# STM32.net
KiCad netlist of a schematic drawn in Altium Designer
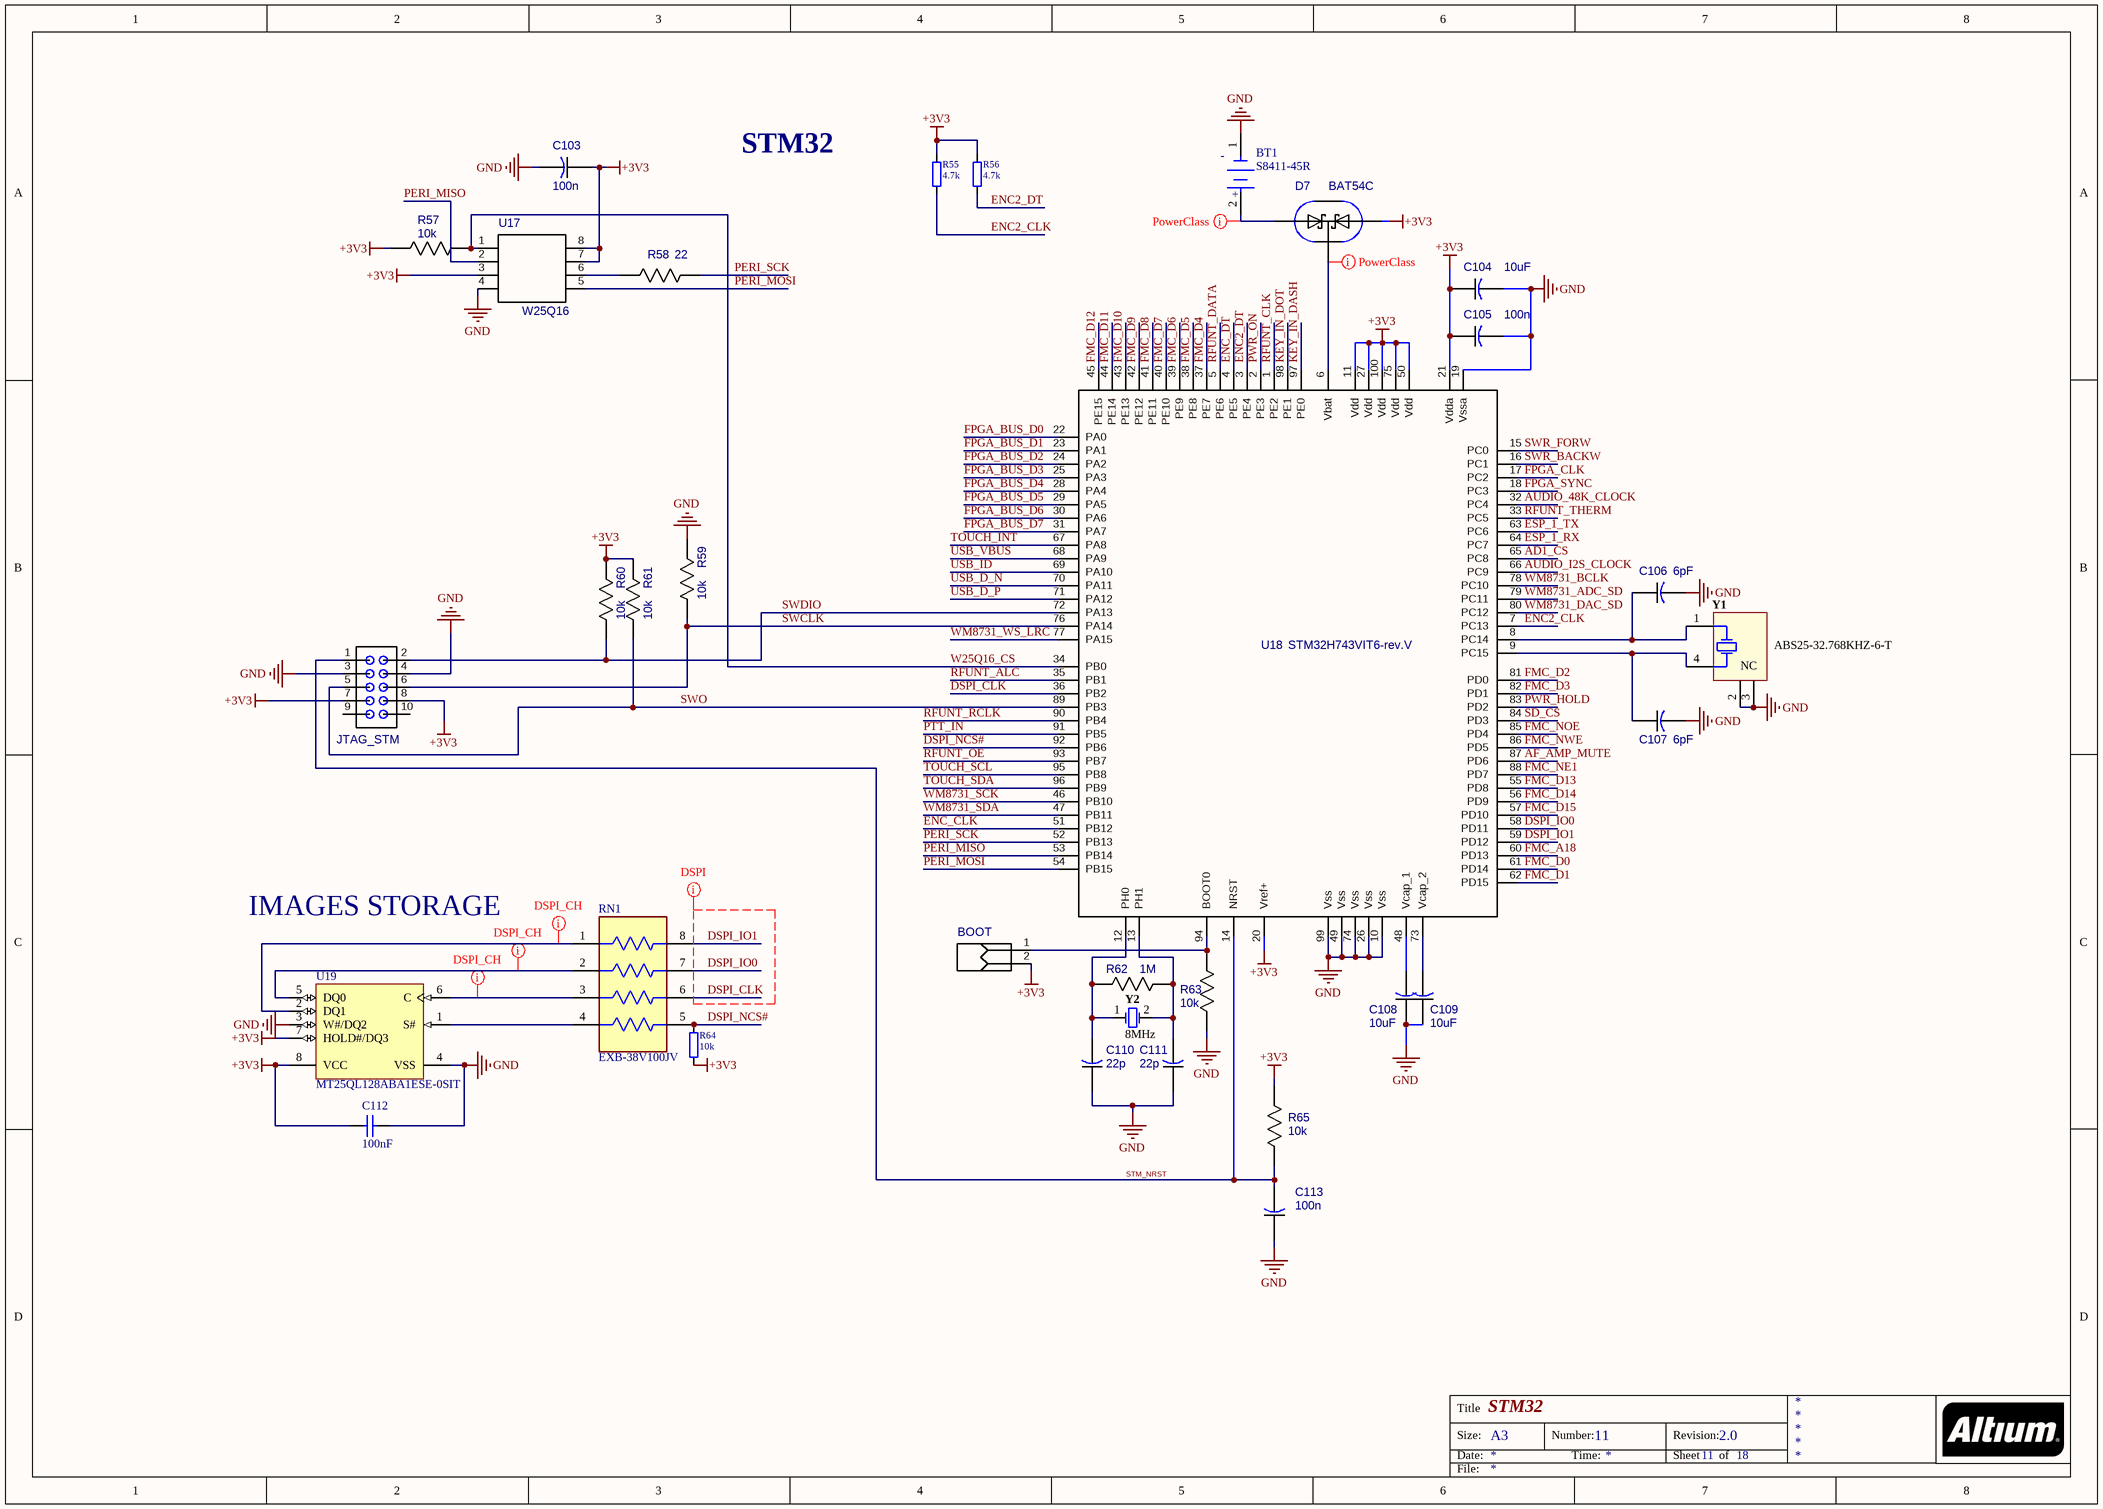
[diagram p0: STM32.SchDoc]

(export (version "E")
  (design (tool "Eeschema 10.0.6"))
  (components
    (comp (ref "BOOT")
      (value "~")
      (footprint "51022-0200")
      (description "2 Pin")
      (libsource (lib "*") (part "51022-0200"))
    )
    (comp (ref "BT1")
      (value "S8411-45R")
      (footprint "FP-S8411-45R-MFG")
      (description "BATTERY HOLDER COIN 12MM SMD")
      (libsource (lib "Altium Content Vault") (part "60d3b5b901a8747834971d0eb8cf3fd"))
    )
    (comp (ref "C103")
      (value "100n")
      (footprint "CAP_0805")
      (description "CAP_0805")
      (libsource (lib "*") (part "CAP_0805"))
    )
    (comp (ref "C104")
      (value "10uF")
      (footprint "CAP_0805")
      (description "CAP_0805")
      (libsource (lib "*") (part "CAP_0805"))
    )
    (comp (ref "C105")
      (value "100n")
      (footprint "CAP_0805")
      (description "CAP_0805")
      (libsource (lib "*") (part "CAP_0805"))
    )
    (comp (ref "C106")
      (value "6pF")
      (footprint "CAP_0805")
      (description "CAP_0805")
      (libsource (lib "*") (part "CAP_0805"))
    )
    (comp (ref "C107")
      (value "6pF")
      (footprint "CAP_0805")
      (description "CAP_0805")
      (libsource (lib "*") (part "CAP_0805"))
    )
    (comp (ref "C108")
      (value "10uF")
      (footprint "CAP_0805")
      (description "CAP_0805")
      (libsource (lib "*") (part "CAP_0805"))
    )
    (comp (ref "C109")
      (value "10uF")
      (footprint "CAP_0805")
      (description "CAP_0805")
      (libsource (lib "*") (part "CAP_0805"))
    )
    (comp (ref "C110")
      (value "22p")
      (footprint "CAP_0805")
      (description "CAP_0805")
      (libsource (lib "*") (part "CAP_0805"))
    )
    (comp (ref "C111")
      (value "22p")
      (footprint "CAP_0805")
      (description "CAP_0805")
      (libsource (lib "*") (part "CAP_0805"))
    )
    (comp (ref "C112")
      (value "100nF")
      (footprint "C-0805")
      (description "Ceramic Multilayer Capacitor")
      (fields (field (name "MANUFACTURER") "Yageo/Phycomp") (field (name "TOLERANCE") "±10%"))
      (libsource (lib "Hristo") (part "C semi"))
    )
    (comp (ref "C113")
      (value "100n")
      (footprint "CAP_0805")
      (description "CAP_0805")
      (libsource (lib "*") (part "CAP_0805"))
    )
    (comp (ref "D7") (value "BAT54C") (footprint "BAT54C") (libsource (lib "*") (part "BAT54C")))
    (comp (ref "JTAG_STM")
      (value "~")
      (footprint "IDC10")
      (description "2*5 Pin")
      (libsource (lib "*") (part "IDC10"))
    )
    (comp (ref "R55")
      (value "4.7k")
      (footprint "R-0603")
      (description "Chip Resistor")
      (fields (field (name "MANUFACTURER") "Yageo/Phycomp"))
      (libsource (lib "Hristo") (part "RES semi"))
    )
    (comp (ref "R56")
      (value "4.7k")
      (footprint "R-0603")
      (description "Chip Resistor")
      (fields (field (name "MANUFACTURER") "Yageo/Phycomp"))
      (libsource (lib "Hristo") (part "RES semi"))
    )
    (comp (ref "R57")
      (value "10k")
      (footprint "RES_0805")
      (description "RES_0805")
      (libsource (lib "*") (part "RES_0805"))
    )
    (comp (ref "R58")
      (value "22")
      (footprint "RES_0805")
      (description "RES_0805")
      (libsource (lib "*") (part "RES_0805"))
    )
    (comp (ref "R59")
      (value "10k")
      (footprint "RES_0805")
      (description "RES_0805")
      (libsource (lib "*") (part "RES_0805"))
    )
    (comp (ref "R60")
      (value "10k")
      (footprint "RES_0805")
      (description "RES_0805")
      (libsource (lib "*") (part "RES_0805"))
    )
    (comp (ref "R61")
      (value "10k")
      (footprint "RES_0805")
      (description "RES_0805")
      (libsource (lib "*") (part "RES_0805"))
    )
    (comp (ref "R62")
      (value "1M")
      (footprint "RES_0805")
      (description "RES_0805")
      (fields (field (name "Comment") "1m"))
      (libsource (lib "*") (part "RES_0805"))
    )
    (comp (ref "R63")
      (value "10k")
      (footprint "RES_0805")
      (description "RES_0805")
      (libsource (lib "*") (part "RES_0805"))
    )
    (comp (ref "R64")
      (value "10k")
      (footprint "R-0603")
      (description "Chip Resistor")
      (fields (field (name "MANUFACTURER") "Yageo/Phycomp"))
      (libsource (lib "Hristo") (part "RES semi"))
    )
    (comp (ref "R65")
      (value "10k")
      (footprint "RES_0805")
      (description "RES_0805")
      (libsource (lib "*") (part "RES_0805"))
    )
    (comp (ref "RN1")
      (value "EXB-38V100JV")
      (footprint "FP-EXB38V-MFG")
      (description "RES ARRAY 4 RES 10 OHM 1206")
      (fields (field (name "TOLERANCE") "5%"))
      (libsource (lib "Altium Content Vault") (part "f16b1fce1dd1e635ae8334856b3239e"))
    )
    (comp (ref "U17") (value "W25Q16") (footprint "W25Q16") (libsource (lib "*") (part "W25Q16")))
    (comp (ref "U18")
      (value "STM32H743VIT6-rev.V")
      (footprint "STM32H743VIT6")
      (description "STM32H743VIT6")
      (libsource (lib "*") (part "STM32H743VIT6"))
    )
    (comp (ref "U19")
      (value "MT25QL128ABA1ESE-0SIT")
      (footprint "MICT-SE-8_M")
      (fields (field (name "MANUFACTURER") "Micron"))
      (libsource (lib "Altium Content Vault") (part "MICT-MT25QL128ABA-SOP2-8"))
    )
    (comp (ref "Y1")
      (value "ABS25-32.768KHZ-6-T")
      (footprint "ABRA-ABS25-4_V")
      (fields (field (name "TOLERANCE") "20PPM") (field (name "MANUFACTURER") "Abracon"))
      (libsource (lib "Altium Content Vault") (part "ABRA-XTAL_1-4-4"))
    )
    (comp (ref "Y2")
      (value "8MHz")
      (footprint "FOX-FOXSLF-2_V")
      (description "Resistance Weld Thru-Hole Crystal, 8 MHz, +/-30 ppm, -20 to 70 degC, 2-Pin THD, RoHS, Bulk")
      (libsource (lib "Altium Content Vault") (part "XTAL-1-2-2"))
    )
  )
  (nets
    (net (code "1") (name "+3V3") (class "Default")
      (node (ref "BOOT") (pin "2") (pinfunction "2_2") (pintype "passive"))
      (node (ref "C103") (pin "1") (pinfunction "1_1") (pintype "passive"))
      (node (ref "C104") (pin "1") (pinfunction "1_1") (pintype "passive"))
      (node (ref "C105") (pin "1") (pinfunction "1_1") (pintype "passive"))
      (node (ref "C112") (pin "1") (pinfunction "1_1") (pintype "passive"))
      (node (ref "D7") (pin "1") (pinfunction "(A1)_1") (pintype "passive"))
      (node (ref "JTAG_STM") (pin "7") (pinfunction "7_7") (pintype "passive"))
      (node (ref "JTAG_STM") (pin "8") (pinfunction "8_8") (pintype "passive"))
      (node (ref "R55") (pin "2") (pinfunction "2_2") (pintype "passive"))
      (node (ref "R56") (pin "2") (pinfunction "2_2") (pintype "passive"))
      (node (ref "R57") (pin "1") (pinfunction "1_1") (pintype "passive"))
      (node (ref "R60") (pin "1") (pinfunction "1_1") (pintype "passive"))
      (node (ref "R61") (pin "1") (pinfunction "1_1") (pintype "passive"))
      (node (ref "R64") (pin "1") (pinfunction "1_1") (pintype "passive"))
      (node (ref "R65") (pin "2") (pinfunction "2_2") (pintype "passive"))
      (node (ref "U17") (pin "3") (pinfunction "WP_3") (pintype "passive"))
      (node (ref "U17") (pin "7") (pinfunction "HOLD_7") (pintype "passive"))
      (node (ref "U17") (pin "8") (pinfunction "VCC_8") (pintype "passive"))
      (node (ref "U18") (pin "100") (pinfunction "Vdd_100") (pintype "passive"))
      (node (ref "U18") (pin "11") (pinfunction "Vdd_11") (pintype "passive"))
      (node (ref "U18") (pin "20") (pinfunction "Vref+_20") (pintype "passive"))
      (node (ref "U18") (pin "21") (pinfunction "Vdda_21") (pintype "passive"))
      (node (ref "U18") (pin "27") (pinfunction "Vdd_27") (pintype "passive"))
      (node (ref "U18") (pin "50") (pinfunction "Vdd_50") (pintype "passive"))
      (node (ref "U18") (pin "75") (pinfunction "Vdd_75") (pintype "passive"))
      (node (ref "U19") (pin "7") (pinfunction "HOLD#/DQ3_7") (pintype "bidirectional"))
      (node (ref "U19") (pin "8") (pinfunction "VCC_8") (pintype "power_in"))
    )
    (net (code "2") (name "/AD1_CS") (class "Default")
      (node (ref "U18") (pin "65") (pinfunction "PC8_65") (pintype "passive"))
    )
    (net (code "3") (name "/AF_AMP_MUTE") (class "Default")
      (node (ref "U18") (pin "87") (pinfunction "PD6_87") (pintype "passive"))
    )
    (net (code "4") (name "/AUDIO_48K_CLOCK") (class "Default")
      (node (ref "U18") (pin "32") (pinfunction "PC4_32") (pintype "passive"))
    )
    (net (code "5") (name "/AUDIO_I2S_CLOCK") (class "Default")
      (node (ref "U18") (pin "66") (pinfunction "PC9_66") (pintype "passive"))
    )
    (net (code "6") (name "/DSPI_CLK") (class "Default")
      (node (ref "RN1") (pin "6") (pinfunction "6_6") (pintype "passive"))
      (node (ref "U18") (pin "36") (pinfunction "PB2_36") (pintype "passive"))
    )
    (net (code "7") (name "/DSPI_IO0") (class "Default")
      (node (ref "RN1") (pin "7") (pinfunction "7_7") (pintype "passive"))
      (node (ref "U18") (pin "58") (pinfunction "PD11_58") (pintype "passive"))
    )
    (net (code "8") (name "/DSPI_IO1") (class "Default")
      (node (ref "RN1") (pin "8") (pinfunction "8_8") (pintype "passive"))
      (node (ref "U18") (pin "59") (pinfunction "PD12_59") (pintype "passive"))
    )
    (net (code "9") (name "/DSPI_NCS#") (class "Default")
      (node (ref "R64") (pin "2") (pinfunction "2_2") (pintype "passive"))
      (node (ref "RN1") (pin "5") (pinfunction "5_5") (pintype "passive"))
      (node (ref "U18") (pin "92") (pinfunction "PB6_92") (pintype "passive"))
    )
    (net (code "10") (name "/ENC2_CLK") (class "Default")
      (node (ref "R55") (pin "1") (pinfunction "1_1") (pintype "passive"))
      (node (ref "U18") (pin "7") (pinfunction "PC13_7") (pintype "passive"))
    )
    (net (code "11") (name "/ENC2_DT") (class "Default")
      (node (ref "R56") (pin "1") (pinfunction "1_1") (pintype "passive"))
      (node (ref "U18") (pin "3") (pinfunction "PE4_3") (pintype "passive"))
    )
    (net (code "12") (name "/ENC_CLK") (class "Default")
      (node (ref "U18") (pin "51") (pinfunction "PB12_51") (pintype "passive"))
    )
    (net (code "13") (name "/ENC_DT") (class "Default")
      (node (ref "U18") (pin "4") (pinfunction "PE5_4") (pintype "passive"))
    )
    (net (code "14") (name "/ESP_1_RX") (class "Default")
      (node (ref "U18") (pin "64") (pinfunction "PC7_64") (pintype "passive"))
    )
    (net (code "15") (name "/ESP_1_TX") (class "Default")
      (node (ref "U18") (pin "63") (pinfunction "PC6_63") (pintype "passive"))
    )
    (net (code "16") (name "/FMC_A18") (class "Default")
      (node (ref "U18") (pin "60") (pinfunction "PD13_60") (pintype "passive"))
    )
    (net (code "17") (name "/FMC_D0") (class "Default")
      (node (ref "U18") (pin "61") (pinfunction "PD14_61") (pintype "passive"))
    )
    (net (code "18") (name "/FMC_D1") (class "Default")
      (node (ref "U18") (pin "62") (pinfunction "PD15_62") (pintype "passive"))
    )
    (net (code "19") (name "/FMC_D2") (class "Default")
      (node (ref "U18") (pin "81") (pinfunction "PD0_81") (pintype "passive"))
    )
    (net (code "20") (name "/FMC_D3") (class "Default")
      (node (ref "U18") (pin "82") (pinfunction "PD1_82") (pintype "passive"))
    )
    (net (code "21") (name "/FMC_D4") (class "Default")
      (node (ref "U18") (pin "37") (pinfunction "PE7_37") (pintype "passive"))
    )
    (net (code "22") (name "/FMC_D5") (class "Default")
      (node (ref "U18") (pin "38") (pinfunction "PE8_38") (pintype "passive"))
    )
    (net (code "23") (name "/FMC_D6") (class "Default")
      (node (ref "U18") (pin "39") (pinfunction "PE9_39") (pintype "passive"))
    )
    (net (code "24") (name "/FMC_D7") (class "Default")
      (node (ref "U18") (pin "40") (pinfunction "PE10_40") (pintype "passive"))
    )
    (net (code "25") (name "/FMC_D8") (class "Default")
      (node (ref "U18") (pin "41") (pinfunction "PE11_41") (pintype "passive"))
    )
    (net (code "26") (name "/FMC_D9") (class "Default")
      (node (ref "U18") (pin "42") (pinfunction "PE12_42") (pintype "passive"))
    )
    (net (code "27") (name "/FMC_D10") (class "Default")
      (node (ref "U18") (pin "43") (pinfunction "PE13_43") (pintype "passive"))
    )
    (net (code "28") (name "/FMC_D11") (class "Default")
      (node (ref "U18") (pin "44") (pinfunction "PE14_44") (pintype "passive"))
    )
    (net (code "29") (name "/FMC_D12") (class "Default")
      (node (ref "U18") (pin "45") (pinfunction "PE15_45") (pintype "passive"))
    )
    (net (code "30") (name "/FMC_D13") (class "Default")
      (node (ref "U18") (pin "55") (pinfunction "PD8_55") (pintype "passive"))
    )
    (net (code "31") (name "/FMC_D14") (class "Default")
      (node (ref "U18") (pin "56") (pinfunction "PD9_56") (pintype "passive"))
    )
    (net (code "32") (name "/FMC_D15") (class "Default")
      (node (ref "U18") (pin "57") (pinfunction "PD10_57") (pintype "passive"))
    )
    (net (code "33") (name "/FMC_NE1") (class "Default")
      (node (ref "U18") (pin "88") (pinfunction "PD7_88") (pintype "passive"))
    )
    (net (code "34") (name "/FMC_NOE") (class "Default")
      (node (ref "U18") (pin "85") (pinfunction "PD4_85") (pintype "passive"))
    )
    (net (code "35") (name "/FMC_NWE") (class "Default")
      (node (ref "U18") (pin "86") (pinfunction "PD5_86") (pintype "passive"))
    )
    (net (code "36") (name "/FPGA_BUS_D0") (class "Default")
      (node (ref "U18") (pin "22") (pinfunction "PA0_22") (pintype "passive"))
    )
    (net (code "37") (name "/FPGA_BUS_D1") (class "Default")
      (node (ref "U18") (pin "23") (pinfunction "PA1_23") (pintype "passive"))
    )
    (net (code "38") (name "/FPGA_BUS_D2") (class "Default")
      (node (ref "U18") (pin "24") (pinfunction "PA2_24") (pintype "passive"))
    )
    (net (code "39") (name "/FPGA_BUS_D3") (class "Default")
      (node (ref "U18") (pin "25") (pinfunction "PA3_25") (pintype "passive"))
    )
    (net (code "40") (name "/FPGA_BUS_D4") (class "Default")
      (node (ref "U18") (pin "28") (pinfunction "PA4_28") (pintype "passive"))
    )
    (net (code "41") (name "/FPGA_BUS_D5") (class "Default")
      (node (ref "U18") (pin "29") (pinfunction "PA5_29") (pintype "passive"))
    )
    (net (code "42") (name "/FPGA_BUS_D6") (class "Default")
      (node (ref "U18") (pin "30") (pinfunction "PA6_30") (pintype "passive"))
    )
    (net (code "43") (name "/FPGA_BUS_D7") (class "Default")
      (node (ref "U18") (pin "31") (pinfunction "PA7_31") (pintype "passive"))
    )
    (net (code "44") (name "/FPGA_CLK") (class "Default")
      (node (ref "U18") (pin "17") (pinfunction "PC2_17") (pintype "passive"))
    )
    (net (code "45") (name "/FPGA_SYNC") (class "Default")
      (node (ref "U18") (pin "18") (pinfunction "PC3_18") (pintype "passive"))
    )
    (net (code "46") (name "/KEY_IN_DASH") (class "Default")
      (node (ref "U18") (pin "97") (pinfunction "PE0_97") (pintype "passive"))
    )
    (net (code "47") (name "/KEY_IN_DOT") (class "Default")
      (node (ref "U18") (pin "98") (pinfunction "PE1_98") (pintype "passive"))
    )
    (net (code "48") (name "/PERI_MISO") (class "Default")
      (node (ref "U17") (pin "2") (pinfunction "SO_2") (pintype "passive"))
      (node (ref "U18") (pin "53") (pinfunction "PB14_53") (pintype "passive"))
    )
    (net (code "49") (name "/PERI_MOSI") (class "Default")
      (node (ref "U17") (pin "5") (pinfunction "SI_5") (pintype "passive"))
      (node (ref "U18") (pin "54") (pinfunction "PB15_54") (pintype "passive"))
    )
    (net (code "50") (name "/PERI_SCK") (class "Default")
      (node (ref "R58") (pin "2") (pinfunction "2_2") (pintype "passive"))
      (node (ref "U18") (pin "52") (pinfunction "PB13_52") (pintype "passive"))
    )
    (net (code "51") (name "/PTT_IN") (class "Default")
      (node (ref "U18") (pin "91") (pinfunction "PB5_91") (pintype "passive"))
    )
    (net (code "52") (name "/PWR_HOLD") (class "Default")
      (node (ref "U18") (pin "83") (pinfunction "PD2_83") (pintype "passive"))
    )
    (net (code "53") (name "/PWR_ON") (class "Default")
      (node (ref "U18") (pin "2") (pinfunction "PE3_2") (pintype "passive"))
    )
    (net (code "54") (name "/RFUNT_ALC") (class "Default")
      (node (ref "U18") (pin "35") (pinfunction "PB1_35") (pintype "passive"))
    )
    (net (code "55") (name "/RFUNT_CLK") (class "Default")
      (node (ref "U18") (pin "1") (pinfunction "PE2_1") (pintype "passive"))
    )
    (net (code "56") (name "/RFUNT_DATA") (class "Default")
      (node (ref "U18") (pin "5") (pinfunction "PE6_5") (pintype "passive"))
    )
    (net (code "57") (name "/RFUNT_OE") (class "Default")
      (node (ref "U18") (pin "93") (pinfunction "PB7_93") (pintype "passive"))
    )
    (net (code "58") (name "/RFUNT_RCLK") (class "Default")
      (node (ref "U18") (pin "90") (pinfunction "PB4_90") (pintype "passive"))
    )
    (net (code "59") (name "/RFUNT_THERM") (class "Default")
      (node (ref "U18") (pin "33") (pinfunction "PC5_33") (pintype "passive"))
    )
    (net (code "60") (name "/SD_CS") (class "Default")
      (node (ref "U18") (pin "84") (pinfunction "PD3_84") (pintype "passive"))
    )
    (net (code "61") (name "/STM_NRST") (class "Default")
      (node (ref "C113") (pin "2") (pinfunction "2_2") (pintype "passive"))
      (node (ref "JTAG_STM") (pin "1") (pinfunction "1_1") (pintype "passive"))
      (node (ref "R65") (pin "1") (pinfunction "1_1") (pintype "passive"))
      (node (ref "U18") (pin "14") (pinfunction "NRST_14") (pintype "passive"))
    )
    (net (code "62") (name "/SWCLK") (class "Default")
      (node (ref "JTAG_STM") (pin "6") (pinfunction "6_6") (pintype "passive"))
      (node (ref "R59") (pin "2") (pinfunction "2_2") (pintype "passive"))
      (node (ref "U18") (pin "76") (pinfunction "PA14_76") (pintype "passive"))
    )
    (net (code "63") (name "/SWDIO") (class "Default")
      (node (ref "JTAG_STM") (pin "2") (pinfunction "2_2") (pintype "passive"))
      (node (ref "R60") (pin "2") (pinfunction "2_2") (pintype "passive"))
      (node (ref "U18") (pin "72") (pinfunction "PA13_72") (pintype "passive"))
    )
    (net (code "64") (name "/SWO") (class "Default")
      (node (ref "JTAG_STM") (pin "5") (pinfunction "5_5") (pintype "passive"))
      (node (ref "R61") (pin "2") (pinfunction "2_2") (pintype "passive"))
      (node (ref "U18") (pin "89") (pinfunction "PB3_89") (pintype "passive"))
    )
    (net (code "65") (name "/SWR_BACKW") (class "Default")
      (node (ref "U18") (pin "16") (pinfunction "PC1_16") (pintype "passive"))
    )
    (net (code "66") (name "/SWR_FORW") (class "Default")
      (node (ref "U18") (pin "15") (pinfunction "PC0_15") (pintype "passive"))
    )
    (net (code "67") (name "/TOUCH_INT") (class "Default")
      (node (ref "U18") (pin "67") (pinfunction "PA8_67") (pintype "passive"))
    )
    (net (code "68") (name "/TOUCH_SCL") (class "Default")
      (node (ref "U18") (pin "95") (pinfunction "PB8_95") (pintype "passive"))
    )
    (net (code "69") (name "/TOUCH_SDA") (class "Default")
      (node (ref "U18") (pin "96") (pinfunction "PB9_96") (pintype "passive"))
    )
    (net (code "70") (name "/USB_D_N") (class "Default")
      (node (ref "U18") (pin "70") (pinfunction "PA11_70") (pintype "passive"))
    )
    (net (code "71") (name "/USB_D_P") (class "Default")
      (node (ref "U18") (pin "71") (pinfunction "PA12_71") (pintype "passive"))
    )
    (net (code "72") (name "/USB_ID") (class "Default")
      (node (ref "U18") (pin "69") (pinfunction "PA10_69") (pintype "passive"))
    )
    (net (code "73") (name "/USB_VBUS") (class "Default")
      (node (ref "U18") (pin "68") (pinfunction "PA9_68") (pintype "passive"))
    )
    (net (code "74") (name "/W25Q16_CS") (class "Default")
      (node (ref "R57") (pin "2") (pinfunction "2_2") (pintype "passive"))
      (node (ref "U17") (pin "1") (pinfunction "CS_1") (pintype "passive"))
      (node (ref "U18") (pin "34") (pinfunction "PB0_34") (pintype "passive"))
    )
    (net (code "75") (name "/WM8731_ADC_SD") (class "Default")
      (node (ref "U18") (pin "79") (pinfunction "PC11_79") (pintype "passive"))
    )
    (net (code "76") (name "/WM8731_BCLK") (class "Default")
      (node (ref "U18") (pin "78") (pinfunction "PC10_78") (pintype "passive"))
    )
    (net (code "77") (name "/WM8731_DAC_SD") (class "Default")
      (node (ref "U18") (pin "80") (pinfunction "PC12_80") (pintype "passive"))
    )
    (net (code "78") (name "/WM8731_SCK") (class "Default")
      (node (ref "U18") (pin "46") (pinfunction "PB10_46") (pintype "passive"))
    )
    (net (code "79") (name "/WM8731_SDA") (class "Default")
      (node (ref "U18") (pin "47") (pinfunction "PB11_47") (pintype "passive"))
    )
    (net (code "80") (name "/WM8731_WS_LRC") (class "Default")
      (node (ref "U18") (pin "77") (pinfunction "PA15_77") (pintype "passive"))
    )
    (net (code "81") (name "GND") (class "Default")
      (node (ref "BT1") (pin "1") (pinfunction "C_1") (pintype "passive"))
      (node (ref "C103") (pin "2") (pinfunction "2_2") (pintype "passive"))
      (node (ref "C104") (pin "2") (pinfunction "2_2") (pintype "passive"))
      (node (ref "C105") (pin "2") (pinfunction "2_2") (pintype "passive"))
      (node (ref "C106") (pin "2") (pinfunction "2_2") (pintype "passive"))
      (node (ref "C107") (pin "2") (pinfunction "2_2") (pintype "passive"))
      (node (ref "C108") (pin "1") (pinfunction "1_1") (pintype "passive"))
      (node (ref "C109") (pin "1") (pinfunction "1_1") (pintype "passive"))
      (node (ref "C110") (pin "1") (pinfunction "1_1") (pintype "passive"))
      (node (ref "C111") (pin "1") (pinfunction "1_1") (pintype "passive"))
      (node (ref "C112") (pin "2") (pinfunction "2_2") (pintype "passive"))
      (node (ref "C113") (pin "1") (pinfunction "1_1") (pintype "passive"))
      (node (ref "JTAG_STM") (pin "3") (pinfunction "3_3") (pintype "passive"))
      (node (ref "JTAG_STM") (pin "4") (pinfunction "4_4") (pintype "passive"))
      (node (ref "R59") (pin "1") (pinfunction "1_1") (pintype "passive"))
      (node (ref "R63") (pin "1") (pinfunction "1_1") (pintype "passive"))
      (node (ref "U17") (pin "4") (pinfunction "GND_4") (pintype "passive"))
      (node (ref "U18") (pin "10") (pinfunction "Vss_10") (pintype "passive"))
      (node (ref "U18") (pin "19") (pinfunction "Vssa_19") (pintype "passive"))
      (node (ref "U18") (pin "26") (pinfunction "Vss_26") (pintype "passive"))
      (node (ref "U18") (pin "49") (pinfunction "Vss_49") (pintype "passive"))
      (node (ref "U18") (pin "74") (pinfunction "Vss_74") (pintype "passive"))
      (node (ref "U18") (pin "99") (pinfunction "Vss_99") (pintype "passive"))
      (node (ref "U19") (pin "3") (pinfunction "W#/DQ2_3") (pintype "bidirectional"))
      (node (ref "U19") (pin "4") (pinfunction "VSS_4") (pintype "power_in"))
      (node (ref "Y1") (pin "2") (pinfunction "NC_2") (pintype "passive"))
      (node (ref "Y1") (pin "3") (pinfunction "NC_3") (pintype "passive"))
    )
    (net (code "82") (name "Net-(BT1-A)") (class "Default")
      (node (ref "BT1") (pin "2") (pinfunction "A_2") (pintype "passive"))
      (node (ref "D7") (pin "2") (pinfunction "(A2)_2") (pintype "passive"))
    )
    (net (code "83") (name "Net-(D7-(K1),(K2))") (class "Default")
      (node (ref "D7") (pin "3") (pinfunction "(K1),(K2)_3") (pintype "passive"))
      (node (ref "U18") (pin "6") (pinfunction "Vbat_6") (pintype "passive"))
    )
    (net (code "84") (name "Net-(U17-CLK)") (class "Default")
      (node (ref "R58") (pin "1") (pinfunction "1_1") (pintype "passive"))
      (node (ref "U17") (pin "6") (pinfunction "CLK_6") (pintype "passive"))
    )
    (net (code "85") (name "Net-(U18-BOOT0)") (class "Default")
      (node (ref "BOOT") (pin "1") (pinfunction "1_1") (pintype "passive"))
      (node (ref "R63") (pin "2") (pinfunction "2_2") (pintype "passive"))
      (node (ref "U18") (pin "94") (pinfunction "BOOT0_94") (pintype "passive"))
    )
    (net (code "86") (name "Net-(U18-PC14)") (class "Default")
      (node (ref "C106") (pin "1") (pinfunction "1_1") (pintype "passive"))
      (node (ref "U18") (pin "8") (pinfunction "PC14_8") (pintype "passive"))
      (node (ref "Y1") (pin "1") (pinfunction "X1_1") (pintype "passive"))
    )
    (net (code "87") (name "Net-(U18-PC15)") (class "Default")
      (node (ref "C107") (pin "1") (pinfunction "1_1") (pintype "passive"))
      (node (ref "U18") (pin "9") (pinfunction "PC15_9") (pintype "passive"))
      (node (ref "Y1") (pin "4") (pinfunction "X2_4") (pintype "passive"))
    )
    (net (code "88") (name "Net-(U18-PH0)") (class "Default")
      (node (ref "C110") (pin "2") (pinfunction "2_2") (pintype "passive"))
      (node (ref "R62") (pin "1") (pinfunction "1_1") (pintype "passive"))
      (node (ref "U18") (pin "12") (pinfunction "PH0_12") (pintype "passive"))
      (node (ref "Y2") (pin "1") (pinfunction "1_1") (pintype "passive"))
    )
    (net (code "89") (name "Net-(U18-PH1)") (class "Default")
      (node (ref "C111") (pin "2") (pinfunction "2_2") (pintype "passive"))
      (node (ref "R62") (pin "2") (pinfunction "2_2") (pintype "passive"))
      (node (ref "U18") (pin "13") (pinfunction "PH1_13") (pintype "passive"))
      (node (ref "Y2") (pin "2") (pinfunction "2_2") (pintype "passive"))
    )
    (net (code "90") (name "Net-(U18-Vcap_1)") (class "Default")
      (node (ref "C108") (pin "2") (pinfunction "2_2") (pintype "passive"))
      (node (ref "U18") (pin "48") (pinfunction "Vcap_1_48") (pintype "passive"))
    )
    (net (code "91") (name "Net-(U18-Vcap_2)") (class "Default")
      (node (ref "C109") (pin "2") (pinfunction "2_2") (pintype "passive"))
      (node (ref "U18") (pin "73") (pinfunction "Vcap_2_73") (pintype "passive"))
    )
    (net (code "92") (name "Net-(U19-C)") (class "Default")
      (node (ref "RN1") (pin "3") (pinfunction "3_3") (pintype "passive"))
      (node (ref "U19") (pin "6") (pinfunction "C_6") (pintype "input"))
    )
    (net (code "93") (name "Net-(U19-DQ0)") (class "Default")
      (node (ref "RN1") (pin "2") (pinfunction "2_2") (pintype "passive"))
      (node (ref "U19") (pin "5") (pinfunction "DQ0_5") (pintype "bidirectional"))
    )
    (net (code "94") (name "Net-(U19-DQ1)") (class "Default")
      (node (ref "RN1") (pin "1") (pinfunction "1_1") (pintype "passive"))
      (node (ref "U19") (pin "2") (pinfunction "DQ1_2") (pintype "bidirectional"))
    )
    (net (code "95") (name "Net-(U19-S#)") (class "Default")
      (node (ref "RN1") (pin "4") (pinfunction "4_4") (pintype "passive"))
      (node (ref "U19") (pin "1") (pinfunction "S#_1") (pintype "input"))
    )
    (net (code "96") (name "unconnected-(JTAG_STM-Pad9)") (class "Default")
      (node (ref "JTAG_STM") (pin "9") (pinfunction "9_9") (pintype "passive"))
    )
    (net (code "97") (name "unconnected-(JTAG_STM-Pad10)") (class "Default")
      (node (ref "JTAG_STM") (pin "10") (pinfunction "10_10") (pintype "passive"))
    )
  )
)
